# filtering-optical-special.net
KiCad netlist of a schematic drawn in Altium Designer
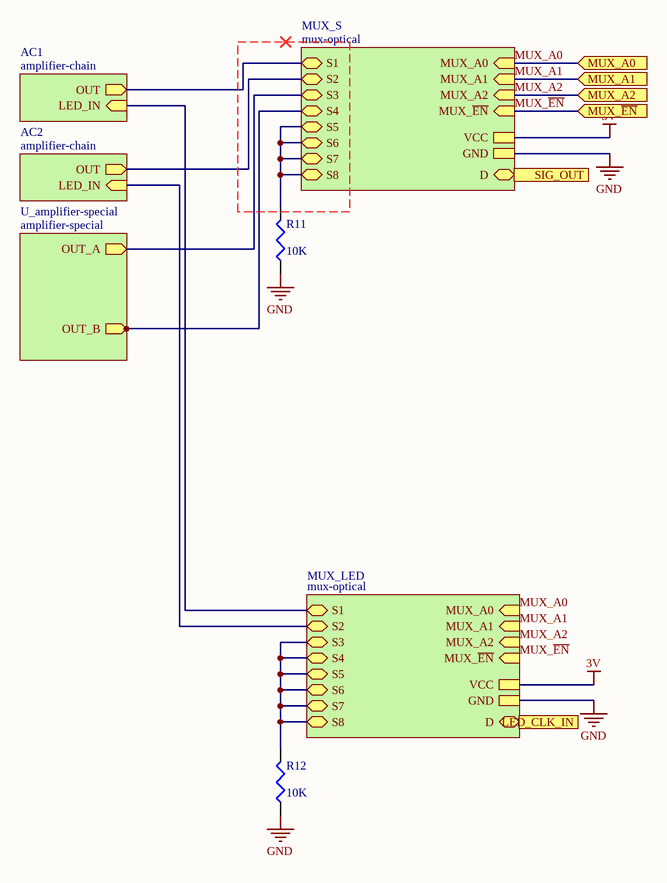
[diagram p0: filtering-optical-special.SchDoc]

(export (version "E")
  (design (tool "Eeschema 10.0.6"))
  (components
    (comp (ref "R11")
      (value "10K")
      (footprint "0402")
      (description "Resistor")
      (fields (field (name "PUBLISHER") "Altium Limited"))
      (libsource (lib "Miscellaneous Devices") (part "Res3"))
    )
    (comp (ref "R12")
      (value "10K")
      (footprint "0402")
      (description "Resistor")
      (fields (field (name "PUBLISHER") "Altium Limited"))
      (libsource (lib "Miscellaneous Devices") (part "Res3"))
    )
  )
  (nets
    (net (code "12") (name "/S3") (class "Default")
      (node (ref "R12") (pin "2") (pinfunction "2_2") (pintype "passive"))
    )
    (net (code "13") (name "/S5") (class "Default")
      (node (ref "R11") (pin "2") (pinfunction "2_2") (pintype "passive"))
    )
    (net (code "16") (name "GND") (class "Default")
      (node (ref "R11") (pin "1") (pinfunction "1_1") (pintype "passive"))
      (node (ref "R12") (pin "1") (pinfunction "1_1") (pintype "passive"))
    )
  )
)
